# 100_POWER_AND_LOADS.net
KiCad netlist of a schematic drawn in Altium Designer
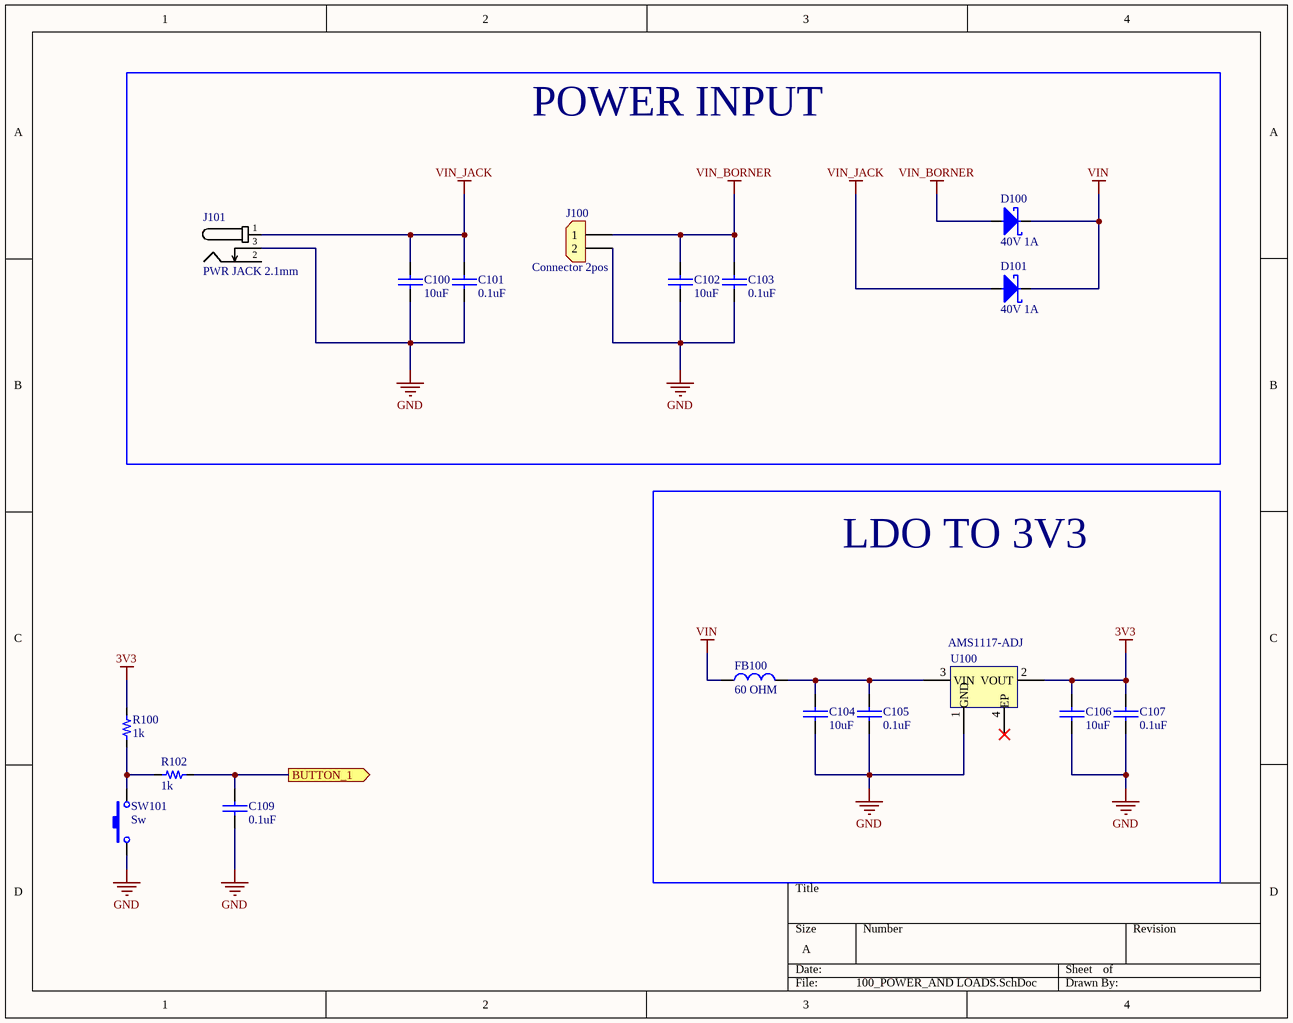
[diagram p0: 100_POWER_AND LOADS.SchDoc]

(export (version "E")
  (design (tool "Eeschema 10.0.6"))
  (components
    (comp (ref "C100")
      (value "10uF")
      (footprint "0603_cap")
      (description "10V 10uF X5R ±10% 0603 Multilayer Ceramic Capacitors MLCC - SMD/SMT ROHS")
      (fields
        (field (name "MANUFACTURER") "CCTC")
        (field (name "MANUFACTURER PART NUMBER") "TCC0603X5R106K100CT")
      )
      (libsource (lib "shared_lib") (part "Cap_10uF_0603_10V"))
    )
    (comp (ref "C101")
      (value "0.1uF")
      (footprint "0603_cap")
      (description "50V 100nF Y5V -20%~+80% 0603 Multilayer Ceramic Capacitors MLCC - SMD/SMT ROHS")
      (fields
        (field (name "MANUFACTURER") "Walsin Tech Corp")
        (field (name "MANUFACTURER PART NUMBER") "0603F104Z500CT")
      )
      (libsource (lib "shared_lib") (part "Cap_0.1uF_0603_50V"))
    )
    (comp (ref "C102")
      (value "10uF")
      (footprint "0603_cap")
      (description "10V 10uF X5R ±10% 0603 Multilayer Ceramic Capacitors MLCC - SMD/SMT ROHS")
      (fields
        (field (name "MANUFACTURER") "CCTC")
        (field (name "MANUFACTURER PART NUMBER") "TCC0603X5R106K100CT")
      )
      (libsource (lib "shared_lib") (part "Cap_10uF_0603_10V"))
    )
    (comp (ref "C103")
      (value "0.1uF")
      (footprint "0603_cap")
      (description "50V 100nF Y5V -20%~+80% 0603 Multilayer Ceramic Capacitors MLCC - SMD/SMT ROHS")
      (fields
        (field (name "MANUFACTURER") "Walsin Tech Corp")
        (field (name "MANUFACTURER PART NUMBER") "0603F104Z500CT")
      )
      (libsource (lib "shared_lib") (part "Cap_0.1uF_0603_50V"))
    )
    (comp (ref "C104")
      (value "10uF")
      (footprint "0603_cap")
      (description "10V 10uF X5R ±10% 0603 Multilayer Ceramic Capacitors MLCC - SMD/SMT ROHS")
      (fields
        (field (name "MANUFACTURER") "CCTC")
        (field (name "MANUFACTURER PART NUMBER") "TCC0603X5R106K100CT")
      )
      (libsource (lib "shared_lib") (part "Cap_10uF_0603_10V"))
    )
    (comp (ref "C105")
      (value "0.1uF")
      (footprint "0603_cap")
      (description "50V 100nF Y5V -20%~+80% 0603 Multilayer Ceramic Capacitors MLCC - SMD/SMT ROHS")
      (fields
        (field (name "MANUFACTURER") "Walsin Tech Corp")
        (field (name "MANUFACTURER PART NUMBER") "0603F104Z500CT")
      )
      (libsource (lib "shared_lib") (part "Cap_0.1uF_0603_50V"))
    )
    (comp (ref "C106")
      (value "10uF")
      (footprint "0603_cap")
      (description "10V 10uF X5R ±10% 0603 Multilayer Ceramic Capacitors MLCC - SMD/SMT ROHS")
      (fields
        (field (name "MANUFACTURER") "CCTC")
        (field (name "MANUFACTURER PART NUMBER") "TCC0603X5R106K100CT")
      )
      (libsource (lib "shared_lib") (part "Cap_10uF_0603_10V"))
    )
    (comp (ref "C107")
      (value "0.1uF")
      (footprint "0603_cap")
      (description "50V 100nF Y5V -20%~+80% 0603 Multilayer Ceramic Capacitors MLCC - SMD/SMT ROHS")
      (fields
        (field (name "MANUFACTURER") "Walsin Tech Corp")
        (field (name "MANUFACTURER PART NUMBER") "0603F104Z500CT")
      )
      (libsource (lib "shared_lib") (part "Cap_0.1uF_0603_50V"))
    )
    (comp (ref "C109")
      (value "0.1uF")
      (footprint "0603_cap")
      (description "50V 100nF Y5V -20%~+80% 0603 Multilayer Ceramic Capacitors MLCC - SMD/SMT ROHS")
      (fields
        (field (name "MANUFACTURER") "Walsin Tech Corp")
        (field (name "MANUFACTURER PART NUMBER") "0603F104Z500CT")
      )
      (libsource (lib "shared_lib") (part "Cap_0.1uF_0603_50V"))
    )
    (comp (ref "D100")
      (value "40V 1A")
      (footprint "SOD_123")
      (description "DIODE SCHOTTKY 40V 1A SOD123F")
      (fields
        (field (name "MANUFACTURER") "Shanghai Prisemi Elec")
        (field (name "MANUFACTURER PART NUMBER") "PSBD1DF40V1H")
      )
      (libsource (lib "shared_lib") (part "D_Schottky_40V_1A_SOD_123F"))
    )
    (comp (ref "D101")
      (value "40V 1A")
      (footprint "SOD_123")
      (description "DIODE SCHOTTKY 40V 1A SOD123F")
      (fields
        (field (name "MANUFACTURER") "Shanghai Prisemi Elec")
        (field (name "MANUFACTURER PART NUMBER") "PSBD1DF40V1H")
      )
      (libsource (lib "shared_lib") (part "D_Schottky_40V_1A_SOD_123F"))
    )
    (comp (ref "FB100")
      (value "60 OHM")
      (footprint "0603_fb")
      (description "2A 1 100mΩ 60Ω@100MHz ±25% 0603 Ferrite Beads ROHS")
      (fields
        (field (name "MANUFACTURER") "TAI-TECH")
        (field (name "MANUFACTURER PART NUMBER") "HCB1608KF-600T20")
      )
      (libsource (lib "shared_lib") (part "FB_60_0603_2A"))
    )
    (comp (ref "J100")
      (value "Connector 2pos")
      (footprint "CON_2x1_TH_5MM")
      (description "2POS 5MM")
      (fields (field (name "MANUFACTURER") "JILN") (field (name "MANUFACTURER PART NUMBER") "JL126-50002G01"))
      (libsource (lib "shared_lib") (part "Con_2x1_TH_5mm"))
    )
    (comp (ref "J101")
      (value "PWR JACK 2.1mm")
      (footprint "CON_POWER_BARREL_2.1MM_3CONN")
      (description "CONN PWR JACK 2X5.5MM SOLDER")
      (fields (field (name "MANUFACTURER") "HCTL") (field (name "MANUFACTURER PART NUMBER") "HC-DC-005-2.0T"))
      (libsource (lib "shared_lib") (part "Con_Power_Jack_2.1mm_3pins"))
    )
    (comp (ref "R100")
      (value "1k")
      (footprint "0603_res")
      (description "RES SMD 1k OHM 5% 1/10W 0603")
      (fields
        (field (name "MANUFACTURER") "FOJAN")
        (field (name "MANUFACTURER PART NUMBER") "FRC0603J102 TS")
      )
      (libsource (lib "shared_lib") (part "Res_1k_0603_1/10W"))
    )
    (comp (ref "R102")
      (value "1k")
      (footprint "0603_res")
      (description "RES SMD 1k OHM 5% 1/10W 0603")
      (fields
        (field (name "MANUFACTURER") "FOJAN")
        (field (name "MANUFACTURER PART NUMBER") "FRC0603J102 TS")
      )
      (libsource (lib "shared_lib") (part "Res_1k_0603_1/10W"))
    )
    (comp (ref "SW101")
      (value "Sw")
      (footprint "Sw_PUSH_4.5x4.5x5mm")
      (description "SWITCH TACTILE SPST-NO 0.05A 12V")
      (fields
        (field (name "MANUFACTURER") "BZCN")
        (field (name "MANUFACTURER PART NUMBER") "TSC015A05026A")
        (field (name "LAST MODIFIED BY") "N-A.Potosi")
      )
      (libsource (lib "shared_lib") (part "Sw_PUSH_4.5x4.5x5.0xmm"))
    )
    (comp (ref "U100")
      (value "AMS1117-ADJ")
      (footprint "SOT_223")
      (fields (field (name "MANUFACTURER") "WPMtek(Wei Pan Microelectronics)"))
      (libsource (lib "shared_lib") (part "LDO_3V3_1A"))
    )
  )
  (nets
    (net (code "1") (name "/BUTTON_1") (class "Default")
      (node (ref "C109") (pin "1") (pinfunction "1_1") (pintype "passive"))
      (node (ref "R102") (pin "2") (pinfunction "2_2") (pintype "passive"))
    )
    (net (code "2") (name "3V3") (class "Default")
      (node (ref "C106") (pin "1") (pinfunction "1_1") (pintype "passive"))
      (node (ref "C107") (pin "1") (pinfunction "1_1") (pintype "passive"))
      (node (ref "R100") (pin "1") (pinfunction "1_1") (pintype "passive"))
      (node (ref "U100") (pin "2") (pinfunction "VOUT_2") (pintype "passive"))
    )
    (net (code "3") (name "GND") (class "Default")
      (node (ref "C100") (pin "2") (pinfunction "2_2") (pintype "passive"))
      (node (ref "C101") (pin "2") (pinfunction "2_2") (pintype "passive"))
      (node (ref "C102") (pin "2") (pinfunction "2_2") (pintype "passive"))
      (node (ref "C103") (pin "2") (pinfunction "2_2") (pintype "passive"))
      (node (ref "C104") (pin "2") (pinfunction "2_2") (pintype "passive"))
      (node (ref "C105") (pin "2") (pinfunction "2_2") (pintype "passive"))
      (node (ref "C106") (pin "2") (pinfunction "2_2") (pintype "passive"))
      (node (ref "C107") (pin "2") (pinfunction "2_2") (pintype "passive"))
      (node (ref "C109") (pin "2") (pinfunction "2_2") (pintype "passive"))
      (node (ref "J100") (pin "2") (pinfunction "2_2") (pintype "passive"))
      (node (ref "J101") (pin "3") (pinfunction "3_3") (pintype "passive"))
      (node (ref "SW101") (pin "1") (pinfunction "1_1") (pintype "passive"))
      (node (ref "U100") (pin "1") (pinfunction "GND_1") (pintype "passive"))
    )
    (net (code "4") (name "Net-(R100-Pad2)") (class "Default")
      (node (ref "R100") (pin "2") (pinfunction "2_2") (pintype "passive"))
      (node (ref "R102") (pin "1") (pinfunction "1_1") (pintype "passive"))
      (node (ref "SW101") (pin "2") (pinfunction "2_2") (pintype "passive"))
    )
    (net (code "5") (name "Net-(U100-VIN)") (class "Default")
      (node (ref "C104") (pin "1") (pinfunction "1_1") (pintype "passive"))
      (node (ref "C105") (pin "1") (pinfunction "1_1") (pintype "passive"))
      (node (ref "FB100") (pin "2") (pinfunction "2_2") (pintype "passive"))
      (node (ref "U100") (pin "3") (pinfunction "VIN_3") (pintype "passive"))
    )
    (net (code "6") (name "VIN") (class "Default")
      (node (ref "D100") (pin "1") (pinfunction "1_1") (pintype "passive"))
      (node (ref "D101") (pin "1") (pinfunction "1_1") (pintype "passive"))
      (node (ref "FB100") (pin "1") (pinfunction "1_1") (pintype "passive"))
    )
    (net (code "7") (name "VIN_BORNER") (class "Default")
      (node (ref "C102") (pin "1") (pinfunction "1_1") (pintype "passive"))
      (node (ref "C103") (pin "1") (pinfunction "1_1") (pintype "passive"))
      (node (ref "D100") (pin "2") (pinfunction "2_2") (pintype "passive"))
      (node (ref "J100") (pin "1") (pinfunction "1_1") (pintype "passive"))
    )
    (net (code "8") (name "VIN_JACK") (class "Default")
      (node (ref "C100") (pin "1") (pinfunction "1_1") (pintype "passive"))
      (node (ref "C101") (pin "1") (pinfunction "1_1") (pintype "passive"))
      (node (ref "D101") (pin "2") (pinfunction "2_2") (pintype "passive"))
      (node (ref "J101") (pin "1") (pinfunction "1_1") (pintype "passive"))
    )
    (net (code "9") (name "unconnected-(J101-Pad2)") (class "Default")
      (node (ref "J101") (pin "2") (pinfunction "2_2") (pintype "passive"))
    )
    (net (code "10") (name "unconnected-(U100-EP-Pad4)") (class "Default")
      (node (ref "U100") (pin "4") (pinfunction "EP_4") (pintype "passive+no_connect"))
    )
  )
)
